# Master_MicroController_1.net
KiCad netlist of a schematic drawn in Altium Designer
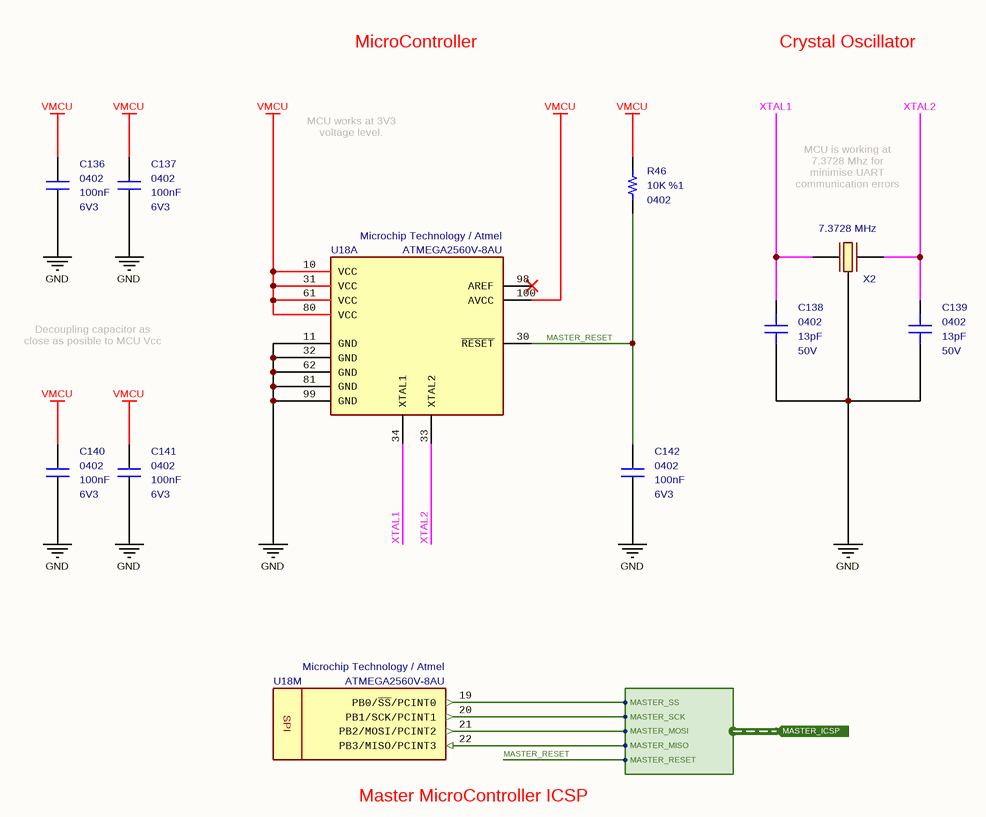
[diagram p0: Master MicroController 1.SchDoc]

(export (version "E")
  (design (tool "Eeschema 10.0.6"))
  (components
    (comp (ref "C136")
      (value "100nF")
      (footprint "CAPACITOR_0402")
      (description "Capacitor - 100nF [0402-6V3] (Ceramic)")
      (fields
        (field (name "MANUFACTURER_PART_NUMBER") "04026D104KAT4A")
        (field (name "MOUSER_PART_NUMBER") "581-04026D104KAT4A")
        (field (name "CASE") "0402")
        (field (name "VOLTAGE") "6V3")
      )
      (libsource (lib "Ovoo_Schematic") (part "Capacitor - 100nF [0402-6V3]"))
    )
    (comp (ref "C137")
      (value "100nF")
      (footprint "CAPACITOR_0402")
      (description "Capacitor - 100nF [0402-6V3] (Ceramic)")
      (fields
        (field (name "MANUFACTURER_PART_NUMBER") "04026D104KAT4A")
        (field (name "MOUSER_PART_NUMBER") "581-04026D104KAT4A")
        (field (name "CASE") "0402")
        (field (name "VOLTAGE") "6V3")
      )
      (libsource (lib "Ovoo_Schematic") (part "Capacitor - 100nF [0402-6V3]"))
    )
    (comp (ref "C138")
      (value "13pF")
      (footprint "CAPACITOR_0402")
      (description "Capacitor - 13pF [0402] (Ceramic)")
      (fields
        (field (name "MANUFACTURER_PART_NUMBER") "CBR04C130F5GAC")
        (field (name "MOUSER_PART_NUMBER") "80-CBR04C130F5GAC")
        (field (name "VOLTAGE") "50V")
        (field (name "CASE") "0402")
      )
      (libsource (lib "Ovoo_Schematic") (part "Capacitor - 13pF [0402-50V)"))
    )
    (comp (ref "C139")
      (value "13pF")
      (footprint "CAPACITOR_0402")
      (description "Capacitor - 13pF [0402] (Ceramic)")
      (fields
        (field (name "MANUFACTURER_PART_NUMBER") "CBR04C130F5GAC")
        (field (name "MOUSER_PART_NUMBER") "80-CBR04C130F5GAC")
        (field (name "VOLTAGE") "50V")
        (field (name "CASE") "0402")
      )
      (libsource (lib "Ovoo_Schematic") (part "Capacitor - 13pF [0402-50V)"))
    )
    (comp (ref "C140")
      (value "100nF")
      (footprint "CAPACITOR_0402")
      (description "Capacitor - 100nF [0402-6V3] (Ceramic)")
      (fields
        (field (name "MANUFACTURER_PART_NUMBER") "04026D104KAT4A")
        (field (name "MOUSER_PART_NUMBER") "581-04026D104KAT4A")
        (field (name "CASE") "0402")
        (field (name "VOLTAGE") "6V3")
      )
      (libsource (lib "Ovoo_Schematic") (part "Capacitor - 100nF [0402-6V3]"))
    )
    (comp (ref "C141")
      (value "100nF")
      (footprint "CAPACITOR_0402")
      (description "Capacitor - 100nF [0402-6V3] (Ceramic)")
      (fields
        (field (name "MANUFACTURER_PART_NUMBER") "04026D104KAT4A")
        (field (name "MOUSER_PART_NUMBER") "581-04026D104KAT4A")
        (field (name "CASE") "0402")
        (field (name "VOLTAGE") "6V3")
      )
      (libsource (lib "Ovoo_Schematic") (part "Capacitor - 100nF [0402-6V3]"))
    )
    (comp (ref "C142")
      (value "100nF")
      (footprint "CAPACITOR_0402")
      (description "Capacitor - 100nF [0402-6V3] (Ceramic)")
      (fields
        (field (name "MANUFACTURER_PART_NUMBER") "04026D104KAT4A")
        (field (name "MOUSER_PART_NUMBER") "581-04026D104KAT4A")
        (field (name "CASE") "0402")
        (field (name "VOLTAGE") "6V3")
      )
      (libsource (lib "Ovoo_Schematic") (part "Capacitor - 100nF [0402-6V3]"))
    )
    (comp (ref "R46")
      (value "10K")
      (footprint "RESISTOR_0402")
      (description "Thick Film Resistors - SMD 1/16 W 10 Kohms 1%")
      (fields
        (field (name "MANUFACTURER_PART_NUMBER") "CRCW040210K0FKED")
        (field (name "MOUSER_PART_NUMBER") "71-CRCW0402-10K-E3")
        (field (name "TOLERANCE") "%1")
        (field (name "CASE") "0402")
      )
      (libsource (lib "Ovoo_Schematic") (part "Resistor - 10K"))
    )
    (comp (ref "U18")
      (value "8-bit MicroController")
      (footprint "TQFP100")
      (description "8-bit Microcontrollers - MCU 256kB Flash 4kB EEPROM 86 I/O Pins")
      (fields
        (field (name "MOUSER_PART_NUMBER") "556-ATMEGA2560V8AU")
        (field (name "MANUFACTURER_PART_NUMBER") "ATMEGA2560V-8AU")
        (field (name "MANUFACTURER_NAME") "Microchip Technology / Atmel")
      )
      (libsource (lib "Ovoo_Library") (part "IC - ATMEGA2560V-8AU"))
    )
    (comp (ref "X2")
      (value "7.3728 MHz")
      (footprint "ABRACON_CRYSTAL")
      (description "Crystals 7.3728MHz 18pF -40C +85C")
      (fields
        (field (name "MANUFACTURER PART NUMBER") "ABMM2-7.3728MHZ-E2-T")
        (field (name "MOUSER PART NUMBER") "815-ABMM2-7.3-E2-T")
      )
      (libsource (lib "Ovoo_Schematic") (part "Crystal - 7.3728 MHz (Abracon)"))
    )
  )
  (nets
    (net (code "2") (name "/MASTER_MISO") (class "Default")
      (node (ref "U18") (pin "22") (pinfunction "PB3/MISO/PCINT3_22") (pintype "input"))
    )
    (net (code "3") (name "/MASTER_MOSI") (class "Default")
      (node (ref "U18") (pin "21") (pinfunction "PB2/MOSI/PCINT2_21") (pintype "output"))
    )
    (net (code "4") (name "/MASTER_RESET") (class "Default")
      (node (ref "C142") (pin "2") (pinfunction "2_2") (pintype "passive"))
      (node (ref "R46") (pin "1") (pinfunction "1_1") (pintype "passive"))
      (node (ref "U18") (pin "30") (pinfunction "~{RESET}_30") (pintype "passive"))
    )
    (net (code "5") (name "/MASTER_SCK") (class "Default")
      (node (ref "U18") (pin "20") (pinfunction "PB1/SCK/PCINT1_20") (pintype "output"))
    )
    (net (code "6") (name "/MASTER_SS") (class "Default")
      (node (ref "U18") (pin "19") (pinfunction "PB0/~{SS}/PCINT0_19") (pintype "output"))
    )
    (net (code "7") (name "/XTAL1") (class "Default")
      (node (ref "C138") (pin "2") (pinfunction "2_2") (pintype "passive"))
      (node (ref "U18") (pin "34") (pinfunction "XTAL1_34") (pintype "passive"))
      (node (ref "X2") (pin "3") (pinfunction "OUT/IN_3") (pintype "passive"))
    )
    (net (code "8") (name "/XTAL2") (class "Default")
      (node (ref "C139") (pin "2") (pinfunction "2_2") (pintype "passive"))
      (node (ref "U18") (pin "33") (pinfunction "XTAL2_33") (pintype "passive"))
      (node (ref "X2") (pin "1") (pinfunction "IN/OUT_1") (pintype "passive"))
    )
    (net (code "10") (name "GND") (class "Default")
      (node (ref "C136") (pin "1") (pinfunction "1_1") (pintype "passive"))
      (node (ref "C137") (pin "1") (pinfunction "1_1") (pintype "passive"))
      (node (ref "C138") (pin "1") (pinfunction "1_1") (pintype "passive"))
      (node (ref "C139") (pin "1") (pinfunction "1_1") (pintype "passive"))
      (node (ref "C140") (pin "1") (pinfunction "1_1") (pintype "passive"))
      (node (ref "C141") (pin "1") (pinfunction "1_1") (pintype "passive"))
      (node (ref "C142") (pin "1") (pinfunction "1_1") (pintype "passive"))
      (node (ref "U18") (pin "11") (pinfunction "GND_11") (pintype "passive"))
      (node (ref "U18") (pin "32") (pinfunction "GND_32") (pintype "passive"))
      (node (ref "U18") (pin "62") (pinfunction "GND_62") (pintype "passive"))
      (node (ref "U18") (pin "81") (pinfunction "GND_81") (pintype "passive"))
      (node (ref "U18") (pin "99") (pinfunction "GND_99") (pintype "passive"))
      (node (ref "X2") (pin "2") (pinfunction "GND_2") (pintype "passive"))
    )
    (net (code "11") (name "VMCU") (class "Default")
      (node (ref "C136") (pin "2") (pinfunction "2_2") (pintype "passive"))
      (node (ref "C137") (pin "2") (pinfunction "2_2") (pintype "passive"))
      (node (ref "C140") (pin "2") (pinfunction "2_2") (pintype "passive"))
      (node (ref "C141") (pin "2") (pinfunction "2_2") (pintype "passive"))
      (node (ref "R46") (pin "2") (pinfunction "2_2") (pintype "passive"))
      (node (ref "U18") (pin "10") (pinfunction "VCC_10") (pintype "power_in"))
      (node (ref "U18") (pin "100") (pinfunction "AVCC_100") (pintype "passive"))
      (node (ref "U18") (pin "31") (pinfunction "VCC_31") (pintype "power_in"))
      (node (ref "U18") (pin "61") (pinfunction "VCC_61") (pintype "power_in"))
      (node (ref "U18") (pin "80") (pinfunction "VCC_80") (pintype "power_in"))
    )
    (net (code "12") (name "unconnected-(U18A-AREF-Pad98)") (class "Default")
      (node (ref "U18") (pin "98") (pinfunction "AREF_98") (pintype "passive+no_connect"))
    )
    (net (code "13") (name "unconnected-(X2-GND-Pad4)") (class "Default")
      (node (ref "X2") (pin "4") (pinfunction "GND_4") (pintype "passive"))
    )
  )
)
